# seven_segment.net
KiCad netlist of a schematic drawn in Altium Designer
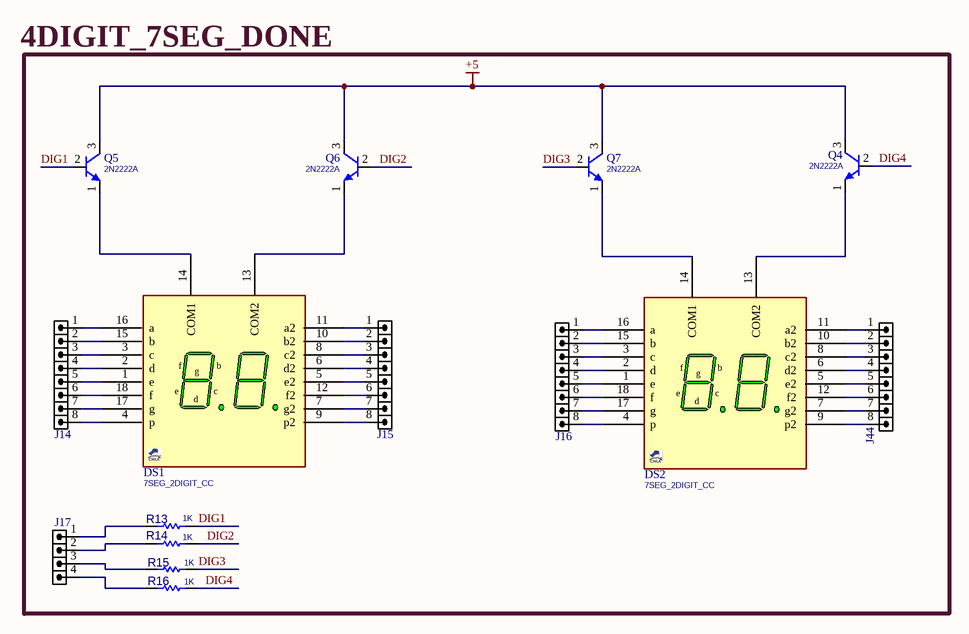
[diagram p0: seven_segment.SchDoc]

(export (version "E")
  (design (tool "Eeschema 10.0.6"))
  (components
    (comp (ref "DS1")
      (value "7SEG_2DIGIT_CC")
      (footprint "7SEGX2_16")
      (description "7SEGMENT, 2DIGIT, common cathode")
      (libsource (lib "AvrDevelopmentBoard_1") (part "7SEG_2DIGIT_CC"))
    )
    (comp (ref "DS2")
      (value "7SEG_2DIGIT_CC")
      (footprint "7SEGX2_16")
      (description "7SEGMENT, 2DIGIT, common cathode")
      (libsource (lib "AvrDevelopmentBoard_1") (part "7SEG_2DIGIT_CC"))
    )
    (comp (ref "J14")
      (value "HDR1X8")
      (footprint "HDR_M_1X8")
      (description "CONN, HEADER, Male, pitch: 2.54mm, 8POS")
      (libsource (lib "") (part "HDR_M_1X8_1"))
    )
    (comp (ref "J15")
      (value "HDR1X8")
      (footprint "HDR_M_1X8")
      (description "CONN, HEADER, Male, pitch: 2.54mm, 8POS")
      (libsource (lib "conn_header_2.54mm_st") (part "HDR_M_1X8"))
    )
    (comp (ref "J16")
      (value "HDR1X8")
      (footprint "HDR_M_1X8")
      (description "CONN, HEADER, Male, pitch: 2.54mm, 8POS")
      (libsource (lib "") (part "HDR_M_1X8_1"))
    )
    (comp (ref "J17")
      (value "HDR1X4")
      (footprint "HDR_M_1X4")
      (description "CONN, HEADER, Male, pitch: 2.54mm, 4POS")
      (libsource (lib "conn_header_2.54mm_st") (part "HDR_M_1X4"))
    )
    (comp (ref "J44")
      (value "HDR1X8")
      (footprint "HDR_M_1X8")
      (description "CONN, HEADER, Male, pitch: 2.54mm, 8POS")
      (libsource (lib "conn_header_2.54mm_st") (part "HDR_M_1X8"))
    )
    (comp (ref "Q4")
      (value "2N2222A")
      (footprint "TO92_3")
      (description "BJT, NPN, 40v, 0.6A, THD, TO92")
      (fields (field (name "MANF") "DIOTEC"))
      (libsource (lib "transistor_bjt") (part "NPN_2N2222A_TO92"))
    )
    (comp (ref "Q5")
      (value "2N2222A")
      (footprint "TO92_3")
      (description "BJT, NPN, 40v, 0.6A, THD, TO92")
      (fields (field (name "MANF") "DIOTEC"))
      (libsource (lib "transistor_bjt") (part "NPN_2N2222A_TO92"))
    )
    (comp (ref "Q6")
      (value "2N2222A")
      (footprint "TO92_3")
      (description "BJT, NPN, 40v, 0.6A, THD, TO92")
      (fields (field (name "MANF") "DIOTEC"))
      (libsource (lib "transistor_bjt") (part "NPN_2N2222A_TO92"))
    )
    (comp (ref "Q7")
      (value "2N2222A")
      (footprint "TO92_3")
      (description "BJT, NPN, 40v, 0.6A, THD, TO92")
      (fields (field (name "MANF") "DIOTEC"))
      (libsource (lib "transistor_bjt") (part "NPN_2N2222A_TO92"))
    )
    (comp (ref "R13")
      (value "1K")
      (footprint "R025W_AX04")
      (description "RESISTOR, THD")
      (fields (field (name "MANF_P#") "RK73H1ETTP4701F") (field (name "MANF") "KOA SPEER"))
      (libsource (lib "passive_thd") (part "RES_THD"))
    )
    (comp (ref "R14")
      (value "1K")
      (footprint "R025W_AX04")
      (description "RESISTOR, THD")
      (fields (field (name "MANF_P#") "RK73H1ETTP4701F") (field (name "MANF") "KOA SPEER"))
      (libsource (lib "passive_thd") (part "RES_THD"))
    )
    (comp (ref "R15")
      (value "1K")
      (footprint "R025W_AX04")
      (description "RESISTOR, THD")
      (fields (field (name "MANF_P#") "RK73H1ETTP4701F") (field (name "MANF") "KOA SPEER"))
      (libsource (lib "passive_thd") (part "RES_THD"))
    )
    (comp (ref "R16")
      (value "1K")
      (footprint "R025W_AX04")
      (description "RESISTOR, THD")
      (fields (field (name "MANF_P#") "RK73H1ETTP4701F") (field (name "MANF") "KOA SPEER"))
      (libsource (lib "passive_thd") (part "RES_THD"))
    )
  )
  (nets
    (net (code "1") (name "+5") (class "Default")
      (node (ref "Q4") (pin "3") (pinfunction "C_3") (pintype "passive"))
      (node (ref "Q5") (pin "3") (pinfunction "C_3") (pintype "passive"))
      (node (ref "Q6") (pin "3") (pinfunction "C_3") (pintype "passive"))
      (node (ref "Q7") (pin "3") (pinfunction "C_3") (pintype "passive"))
    )
    (net (code "2") (name "/DIG1") (class "Default")
      (node (ref "Q5") (pin "2") (pinfunction "B_2") (pintype "passive"))
      (node (ref "R13") (pin "1") (pinfunction "1_1") (pintype "passive"))
    )
    (net (code "3") (name "/DIG2") (class "Default")
      (node (ref "Q6") (pin "2") (pinfunction "B_2") (pintype "passive"))
      (node (ref "R14") (pin "1") (pinfunction "1_1") (pintype "passive"))
    )
    (net (code "4") (name "/DIG3") (class "Default")
      (node (ref "Q7") (pin "2") (pinfunction "B_2") (pintype "passive"))
      (node (ref "R15") (pin "1") (pinfunction "1_1") (pintype "passive"))
    )
    (net (code "5") (name "/DIG4") (class "Default")
      (node (ref "Q4") (pin "2") (pinfunction "B_2") (pintype "passive"))
      (node (ref "R16") (pin "1") (pinfunction "1_1") (pintype "passive"))
    )
    (net (code "6") (name "Net-(DS1-COM1)") (class "Default")
      (node (ref "DS1") (pin "14") (pinfunction "COM1_14") (pintype "passive"))
      (node (ref "Q5") (pin "1") (pinfunction "E_1") (pintype "passive"))
    )
    (net (code "7") (name "Net-(DS1-COM2)") (class "Default")
      (node (ref "DS1") (pin "13") (pinfunction "COM2_13") (pintype "passive"))
      (node (ref "Q6") (pin "1") (pinfunction "E_1") (pintype "passive"))
    )
    (net (code "8") (name "Net-(DS1-a)") (class "Default")
      (node (ref "DS1") (pin "16") (pinfunction "a_16") (pintype "passive"))
      (node (ref "J14") (pin "1") (pinfunction "1_1") (pintype "passive"))
    )
    (net (code "9") (name "Net-(DS1-a2)") (class "Default")
      (node (ref "DS1") (pin "11") (pinfunction "a2_11") (pintype "passive"))
      (node (ref "J15") (pin "1") (pinfunction "1_1") (pintype "passive"))
    )
    (net (code "10") (name "Net-(DS1-b)") (class "Default")
      (node (ref "DS1") (pin "15") (pinfunction "b_15") (pintype "passive"))
      (node (ref "J14") (pin "2") (pinfunction "2_2") (pintype "passive"))
    )
    (net (code "11") (name "Net-(DS1-b2)") (class "Default")
      (node (ref "DS1") (pin "10") (pinfunction "b2_10") (pintype "passive"))
      (node (ref "J15") (pin "2") (pinfunction "2_2") (pintype "passive"))
    )
    (net (code "12") (name "Net-(DS1-c)") (class "Default")
      (node (ref "DS1") (pin "3") (pinfunction "c_3") (pintype "passive"))
      (node (ref "J14") (pin "3") (pinfunction "3_3") (pintype "passive"))
    )
    (net (code "13") (name "Net-(DS1-c2)") (class "Default")
      (node (ref "DS1") (pin "8") (pinfunction "c2_8") (pintype "passive"))
      (node (ref "J15") (pin "3") (pinfunction "3_3") (pintype "passive"))
    )
    (net (code "14") (name "Net-(DS1-d)") (class "Default")
      (node (ref "DS1") (pin "2") (pinfunction "d_2") (pintype "passive"))
      (node (ref "J14") (pin "4") (pinfunction "4_4") (pintype "passive"))
    )
    (net (code "15") (name "Net-(DS1-d2)") (class "Default")
      (node (ref "DS1") (pin "6") (pinfunction "d2_6") (pintype "passive"))
      (node (ref "J15") (pin "4") (pinfunction "4_4") (pintype "passive"))
    )
    (net (code "16") (name "Net-(DS1-e)") (class "Default")
      (node (ref "DS1") (pin "1") (pinfunction "e_1") (pintype "passive"))
      (node (ref "J14") (pin "5") (pinfunction "5_5") (pintype "passive"))
    )
    (net (code "17") (name "Net-(DS1-e2)") (class "Default")
      (node (ref "DS1") (pin "5") (pinfunction "e2_5") (pintype "passive"))
      (node (ref "J15") (pin "5") (pinfunction "5_5") (pintype "passive"))
    )
    (net (code "18") (name "Net-(DS1-f)") (class "Default")
      (node (ref "DS1") (pin "18") (pinfunction "f_18") (pintype "passive"))
      (node (ref "J14") (pin "6") (pinfunction "6_6") (pintype "passive"))
    )
    (net (code "19") (name "Net-(DS1-f2)") (class "Default")
      (node (ref "DS1") (pin "12") (pinfunction "f2_12") (pintype "passive"))
      (node (ref "J15") (pin "6") (pinfunction "6_6") (pintype "passive"))
    )
    (net (code "20") (name "Net-(DS1-g)") (class "Default")
      (node (ref "DS1") (pin "17") (pinfunction "g_17") (pintype "passive"))
      (node (ref "J14") (pin "7") (pinfunction "7_7") (pintype "passive"))
    )
    (net (code "21") (name "Net-(DS1-g2)") (class "Default")
      (node (ref "DS1") (pin "7") (pinfunction "g2_7") (pintype "passive"))
      (node (ref "J15") (pin "7") (pinfunction "7_7") (pintype "passive"))
    )
    (net (code "22") (name "Net-(DS1-p)") (class "Default")
      (node (ref "DS1") (pin "4") (pinfunction "p_4") (pintype "passive"))
      (node (ref "J14") (pin "8") (pinfunction "8_8") (pintype "passive"))
    )
    (net (code "23") (name "Net-(DS1-p2)") (class "Default")
      (node (ref "DS1") (pin "9") (pinfunction "p2_9") (pintype "passive"))
      (node (ref "J15") (pin "8") (pinfunction "8_8") (pintype "passive"))
    )
    (net (code "24") (name "Net-(DS2-COM1)") (class "Default")
      (node (ref "DS2") (pin "14") (pinfunction "COM1_14") (pintype "passive"))
      (node (ref "Q7") (pin "1") (pinfunction "E_1") (pintype "passive"))
    )
    (net (code "25") (name "Net-(DS2-COM2)") (class "Default")
      (node (ref "DS2") (pin "13") (pinfunction "COM2_13") (pintype "passive"))
      (node (ref "Q4") (pin "1") (pinfunction "E_1") (pintype "passive"))
    )
    (net (code "26") (name "Net-(DS2-a)") (class "Default")
      (node (ref "DS2") (pin "16") (pinfunction "a_16") (pintype "passive"))
      (node (ref "J16") (pin "1") (pinfunction "1_1") (pintype "passive"))
    )
    (net (code "27") (name "Net-(DS2-a2)") (class "Default")
      (node (ref "DS2") (pin "11") (pinfunction "a2_11") (pintype "passive"))
      (node (ref "J44") (pin "1") (pinfunction "1_1") (pintype "passive"))
    )
    (net (code "28") (name "Net-(DS2-b)") (class "Default")
      (node (ref "DS2") (pin "15") (pinfunction "b_15") (pintype "passive"))
      (node (ref "J16") (pin "2") (pinfunction "2_2") (pintype "passive"))
    )
    (net (code "29") (name "Net-(DS2-b2)") (class "Default")
      (node (ref "DS2") (pin "10") (pinfunction "b2_10") (pintype "passive"))
      (node (ref "J44") (pin "2") (pinfunction "2_2") (pintype "passive"))
    )
    (net (code "30") (name "Net-(DS2-c)") (class "Default")
      (node (ref "DS2") (pin "3") (pinfunction "c_3") (pintype "passive"))
      (node (ref "J16") (pin "3") (pinfunction "3_3") (pintype "passive"))
    )
    (net (code "31") (name "Net-(DS2-c2)") (class "Default")
      (node (ref "DS2") (pin "8") (pinfunction "c2_8") (pintype "passive"))
      (node (ref "J44") (pin "3") (pinfunction "3_3") (pintype "passive"))
    )
    (net (code "32") (name "Net-(DS2-d)") (class "Default")
      (node (ref "DS2") (pin "2") (pinfunction "d_2") (pintype "passive"))
      (node (ref "J16") (pin "4") (pinfunction "4_4") (pintype "passive"))
    )
    (net (code "33") (name "Net-(DS2-d2)") (class "Default")
      (node (ref "DS2") (pin "6") (pinfunction "d2_6") (pintype "passive"))
      (node (ref "J44") (pin "4") (pinfunction "4_4") (pintype "passive"))
    )
    (net (code "34") (name "Net-(DS2-e)") (class "Default")
      (node (ref "DS2") (pin "1") (pinfunction "e_1") (pintype "passive"))
      (node (ref "J16") (pin "5") (pinfunction "5_5") (pintype "passive"))
    )
    (net (code "35") (name "Net-(DS2-e2)") (class "Default")
      (node (ref "DS2") (pin "5") (pinfunction "e2_5") (pintype "passive"))
      (node (ref "J44") (pin "5") (pinfunction "5_5") (pintype "passive"))
    )
    (net (code "36") (name "Net-(DS2-f)") (class "Default")
      (node (ref "DS2") (pin "18") (pinfunction "f_18") (pintype "passive"))
      (node (ref "J16") (pin "6") (pinfunction "6_6") (pintype "passive"))
    )
    (net (code "37") (name "Net-(DS2-f2)") (class "Default")
      (node (ref "DS2") (pin "12") (pinfunction "f2_12") (pintype "passive"))
      (node (ref "J44") (pin "6") (pinfunction "6_6") (pintype "passive"))
    )
    (net (code "38") (name "Net-(DS2-g)") (class "Default")
      (node (ref "DS2") (pin "17") (pinfunction "g_17") (pintype "passive"))
      (node (ref "J16") (pin "7") (pinfunction "7_7") (pintype "passive"))
    )
    (net (code "39") (name "Net-(DS2-g2)") (class "Default")
      (node (ref "DS2") (pin "7") (pinfunction "g2_7") (pintype "passive"))
      (node (ref "J44") (pin "7") (pinfunction "7_7") (pintype "passive"))
    )
    (net (code "40") (name "Net-(DS2-p)") (class "Default")
      (node (ref "DS2") (pin "4") (pinfunction "p_4") (pintype "passive"))
      (node (ref "J16") (pin "8") (pinfunction "8_8") (pintype "passive"))
    )
    (net (code "41") (name "Net-(DS2-p2)") (class "Default")
      (node (ref "DS2") (pin "9") (pinfunction "p2_9") (pintype "passive"))
      (node (ref "J44") (pin "8") (pinfunction "8_8") (pintype "passive"))
    )
    (net (code "42") (name "Net-(J17-Pad1)") (class "Default")
      (node (ref "J17") (pin "1") (pinfunction "1_1") (pintype "passive"))
      (node (ref "R13") (pin "2") (pinfunction "2_2") (pintype "passive"))
    )
    (net (code "43") (name "Net-(J17-Pad2)") (class "Default")
      (node (ref "J17") (pin "2") (pinfunction "2_2") (pintype "passive"))
      (node (ref "R14") (pin "2") (pinfunction "2_2") (pintype "passive"))
    )
    (net (code "44") (name "Net-(J17-Pad3)") (class "Default")
      (node (ref "J17") (pin "3") (pinfunction "3_3") (pintype "passive"))
      (node (ref "R15") (pin "2") (pinfunction "2_2") (pintype "passive"))
    )
    (net (code "45") (name "Net-(J17-Pad4)") (class "Default")
      (node (ref "J17") (pin "4") (pinfunction "4_4") (pintype "passive"))
      (node (ref "R16") (pin "2") (pinfunction "2_2") (pintype "passive"))
    )
  )
)
